# contactor_connectors.net
KiCad netlist of a schematic drawn in Altium Designer
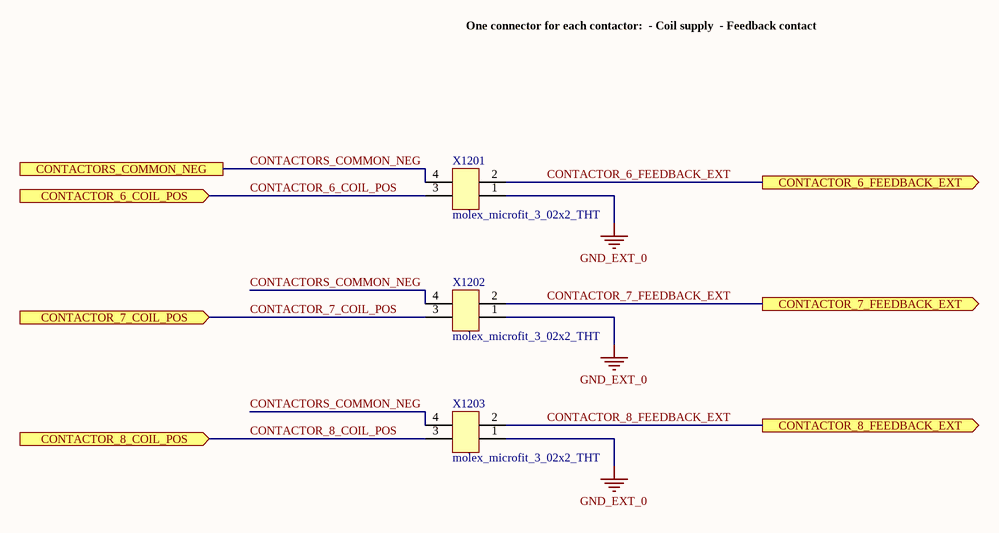
[diagram p0: contactor_connectors.SchDoc]

(export (version "E")
  (design (tool "Eeschema 10.0.6"))
  (components
    (comp (ref "X1201")
      (value "molex_microfit_3_02x2_THT")
      (footprint "MOLEX_MICROFIT_02x2_THT")
      (fields (field (name "MANUFACTURER") "Molex"))
      (libsource (lib "OE750") (part "X2x2"))
    )
    (comp (ref "X1202")
      (value "molex_microfit_3_02x2_THT")
      (footprint "MOLEX_MICROFIT_02x2_THT")
      (fields (field (name "MANUFACTURER") "Molex"))
      (libsource (lib "OE750") (part "X2x2"))
    )
    (comp (ref "X1203")
      (value "molex_microfit_3_02x2_THT")
      (footprint "MOLEX_MICROFIT_02x2_THT")
      (fields (field (name "MANUFACTURER") "Molex"))
      (libsource (lib "OE750") (part "X2x2"))
    )
  )
  (nets
    (net (code "1") (name "/CONTACTORS_COMMON_NEG") (class "Default")
      (node (ref "X1201") (pin "4") (pintype "passive"))
      (node (ref "X1202") (pin "4") (pintype "passive"))
      (node (ref "X1203") (pin "4") (pintype "passive"))
    )
    (net (code "2") (name "/CONTACTOR_6_COIL_POS") (class "Default")
      (node (ref "X1201") (pin "3") (pintype "passive"))
    )
    (net (code "3") (name "/CONTACTOR_6_FEEDBACK_EXT") (class "Default")
      (node (ref "X1201") (pin "2") (pintype "passive"))
    )
    (net (code "4") (name "/CONTACTOR_7_COIL_POS") (class "Default")
      (node (ref "X1202") (pin "3") (pintype "passive"))
    )
    (net (code "5") (name "/CONTACTOR_7_FEEDBACK_EXT") (class "Default")
      (node (ref "X1202") (pin "2") (pintype "passive"))
    )
    (net (code "6") (name "/CONTACTOR_8_COIL_POS") (class "Default")
      (node (ref "X1203") (pin "3") (pintype "passive"))
    )
    (net (code "7") (name "/CONTACTOR_8_FEEDBACK_EXT") (class "Default")
      (node (ref "X1203") (pin "2") (pintype "passive"))
    )
    (net (code "8") (name "GND_EXT_0") (class "Default")
      (node (ref "X1201") (pin "1") (pintype "passive"))
      (node (ref "X1202") (pin "1") (pintype "passive"))
      (node (ref "X1203") (pin "1") (pintype "passive"))
    )
  )
)
